# Radio.net
KiCad netlist of a schematic drawn in Altium Designer
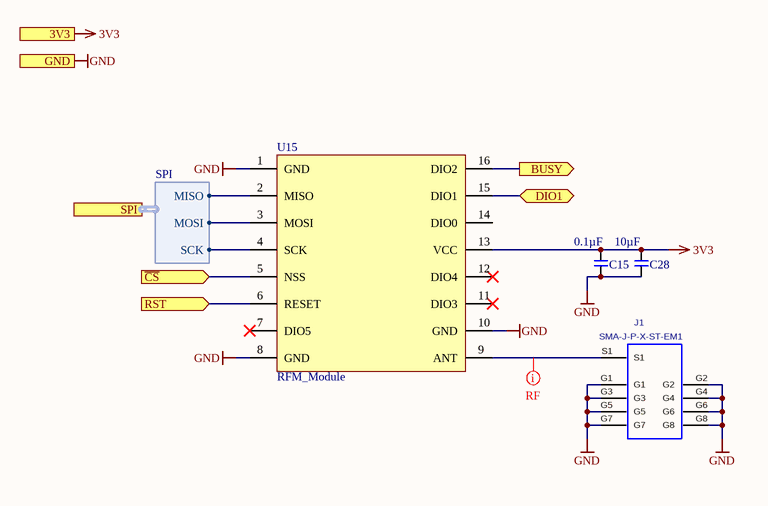
[diagram p0: Radio.SchDoc]

(export (version "E")
  (design (tool "Eeschema 10.0.6"))
  (components
    (comp (ref "C15")
      (value "490-1519-1-ND")
      (footprint "C0603")
      (description "CAP CER 0603 0.1µF X7R 50V 10%")
      (fields
        (field (name "MANUFACTURER") "Murata Electronics North America")
        (field (name "CAPACITANCE (SHORTHAND)") "0.1µF")
      )
      (libsource (lib "Stanford Student Space Initiative") (part "__template_cap"))
    )
    (comp (ref "C28")
      (value "490-13248-1-ND")
      (footprint "C0603")
      (description "CAP CER 10UF 35V X5R 0603 20%")
      (fields
        (field (name "CAPACITANCE (SHORTHAND)") "10µF")
        (field (name "MANUFACTURER") "Murata Electronics North America")
      )
      (libsource (lib "Stanford Student Space Initiative") (part "__template_cap"))
    )
    (comp (ref "J1")
      (value "SMA-J-P-X-ST-EM1")
      (footprint "SMA-J-P-X-ST-EM1")
      (description "SMA STRAIGHT, EDGE MOUNT JACK- 50 OHM")
      (fields (field (name "MANUFACTURER") "SAMTEC") (field (name "CREATED") "APRIL 8 2014 - WENDY XIN"))
      (libsource (lib "Stanford Student Space Initiative") (part "SMA-J-P-X-ST-EM1"))
    )
    (comp (ref "U15")
      (value "RFM_Module")
      (footprint "RFM-22")
      (libsource (lib "Stanford Student Space Initiative") (part "RFM_Module"))
    )
  )
  (nets
    (net (code "2") (name "/BUSY") (class "Default")
      (node (ref "U15") (pin "16") (pinfunction "DIO2_16") (pintype "passive"))
    )
    (net (code "3") (name "/DIO1") (class "Default")
      (node (ref "U15") (pin "15") (pinfunction "DIO1_15") (pintype "passive"))
    )
    (net (code "4") (name "/MISO") (class "Default")
      (node (ref "U15") (pin "2") (pinfunction "MISO_2") (pintype "passive"))
    )
    (net (code "5") (name "/MOSI") (class "Default")
      (node (ref "U15") (pin "3") (pinfunction "MOSI_3") (pintype "passive"))
    )
    (net (code "6") (name "/RST") (class "Default")
      (node (ref "U15") (pin "6") (pinfunction "RESET_6") (pintype "passive"))
    )
    (net (code "7") (name "/SCK") (class "Default")
      (node (ref "U15") (pin "4") (pinfunction "SCK_4") (pintype "passive"))
    )
    (net (code "9") (name "/~{CS}") (class "Default")
      (node (ref "U15") (pin "5") (pinfunction "NSS_5") (pintype "passive"))
    )
    (net (code "10") (name "3V3") (class "Default")
      (node (ref "C15") (pin "1") (pintype "passive"))
      (node (ref "C28") (pin "1") (pintype "passive"))
      (node (ref "U15") (pin "13") (pinfunction "VCC_13") (pintype "passive"))
    )
    (net (code "11") (name "GND") (class "Default")
      (node (ref "C15") (pin "2") (pintype "passive"))
      (node (ref "C28") (pin "2") (pintype "passive"))
      (node (ref "J1") (pin "G1") (pinfunction "G1_G1") (pintype "passive"))
      (node (ref "J1") (pin "G2") (pinfunction "G2_G2") (pintype "passive"))
      (node (ref "J1") (pin "G3") (pinfunction "G3_G3") (pintype "passive"))
      (node (ref "J1") (pin "G4") (pinfunction "G4_G4") (pintype "passive"))
      (node (ref "J1") (pin "G5") (pinfunction "G5_G5") (pintype "passive"))
      (node (ref "J1") (pin "G6") (pinfunction "G6_G6") (pintype "passive"))
      (node (ref "J1") (pin "G7") (pinfunction "G7_G7") (pintype "passive"))
      (node (ref "J1") (pin "G8") (pinfunction "G8_G8") (pintype "passive"))
      (node (ref "U15") (pin "1") (pinfunction "GND_1") (pintype "passive"))
      (node (ref "U15") (pin "10") (pinfunction "GND_10") (pintype "passive"))
      (node (ref "U15") (pin "8") (pinfunction "GND_8") (pintype "passive"))
    )
    (net (code "12") (name "Net-(U15-ANT)") (class "Default")
      (node (ref "J1") (pin "S1") (pinfunction "S1_S1") (pintype "passive"))
      (node (ref "U15") (pin "9") (pinfunction "ANT_9") (pintype "passive"))
    )
    (net (code "13") (name "unconnected-(U15-DIO0-Pad14)") (class "Default")
      (node (ref "U15") (pin "14") (pinfunction "DIO0_14") (pintype "passive"))
    )
    (net (code "14") (name "unconnected-(U15-DIO3-Pad11)") (class "Default")
      (node (ref "U15") (pin "11") (pinfunction "DIO3_11") (pintype "passive+no_connect"))
    )
    (net (code "15") (name "unconnected-(U15-DIO4-Pad12)") (class "Default")
      (node (ref "U15") (pin "12") (pinfunction "DIO4_12") (pintype "passive+no_connect"))
    )
    (net (code "16") (name "unconnected-(U15-DIO5-Pad7)") (class "Default")
      (node (ref "U15") (pin "7") (pinfunction "DIO5_7") (pintype "passive+no_connect"))
    )
  )
)
